# FPGA_POWER.net
KiCad netlist of a schematic drawn in Altium Designer
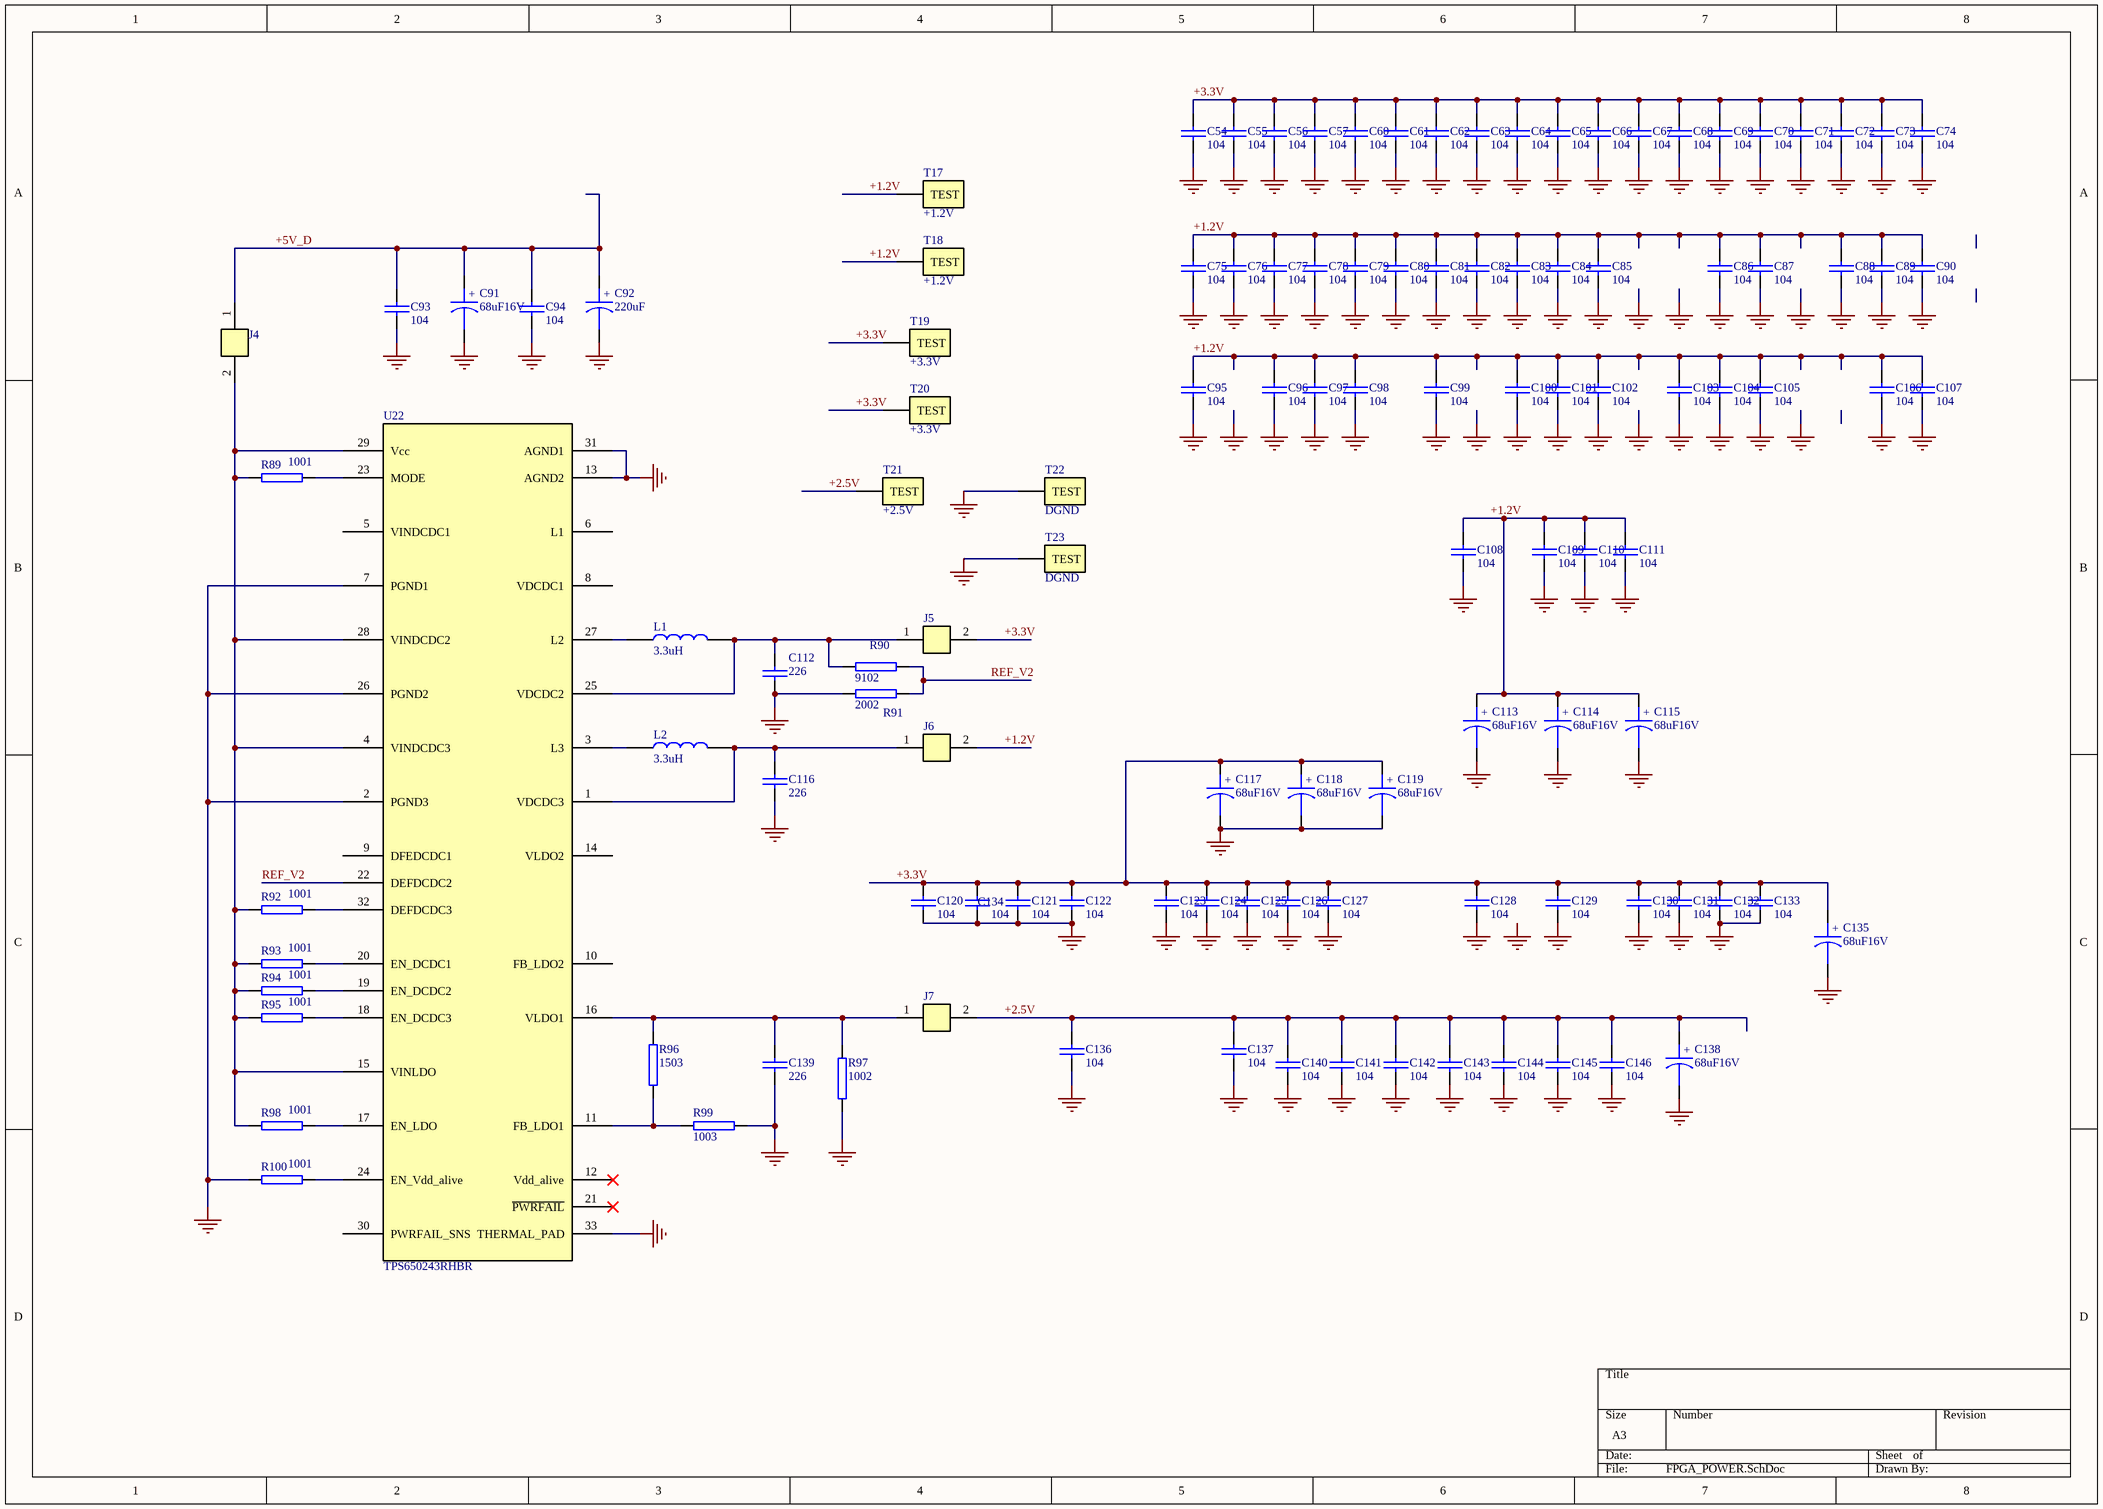
[diagram p0: FPGA_POWER.SchDoc]

(export (version "E")
  (design (tool "Eeschema 10.0.6"))
  (components
    (comp (ref "C54")
      (value "104")
      (footprint "0805C")
      (description "Capacitor")
      (libsource (lib "*") (part "CAP"))
    )
    (comp (ref "C55")
      (value "104")
      (footprint "0402C")
      (description "Capacitor")
      (libsource (lib "*") (part "CAP"))
    )
    (comp (ref "C56")
      (value "104")
      (footprint "0402C")
      (description "Capacitor")
      (libsource (lib "*") (part "CAP"))
    )
    (comp (ref "C57")
      (value "104")
      (footprint "0402C")
      (description "Capacitor")
      (libsource (lib "*") (part "CAP"))
    )
    (comp (ref "C60")
      (value "104")
      (footprint "0402C")
      (description "Capacitor")
      (libsource (lib "*") (part "CAP"))
    )
    (comp (ref "C61")
      (value "104")
      (footprint "0402C")
      (description "Capacitor")
      (libsource (lib "*") (part "CAP"))
    )
    (comp (ref "C62")
      (value "104")
      (footprint "0402C")
      (description "Capacitor")
      (libsource (lib "*") (part "CAP"))
    )
    (comp (ref "C63")
      (value "104")
      (footprint "0402C")
      (description "Capacitor")
      (libsource (lib "*") (part "CAP"))
    )
    (comp (ref "C64")
      (value "104")
      (footprint "0402C")
      (description "Capacitor")
      (libsource (lib "*") (part "CAP"))
    )
    (comp (ref "C65")
      (value "104")
      (footprint "0402C")
      (description "Capacitor")
      (libsource (lib "*") (part "CAP"))
    )
    (comp (ref "C66")
      (value "104")
      (footprint "0402C")
      (description "Capacitor")
      (libsource (lib "*") (part "CAP"))
    )
    (comp (ref "C67")
      (value "104")
      (footprint "0402C")
      (description "Capacitor")
      (libsource (lib "*") (part "CAP"))
    )
    (comp (ref "C68")
      (value "104")
      (footprint "0402C")
      (description "Capacitor")
      (libsource (lib "*") (part "CAP"))
    )
    (comp (ref "C69")
      (value "104")
      (footprint "0402C")
      (description "Capacitor")
      (libsource (lib "*") (part "CAP"))
    )
    (comp (ref "C70")
      (value "104")
      (footprint "0402C")
      (description "Capacitor")
      (libsource (lib "*") (part "CAP"))
    )
    (comp (ref "C71")
      (value "104")
      (footprint "0402C")
      (description "Capacitor")
      (libsource (lib "*") (part "CAP"))
    )
    (comp (ref "C72")
      (value "104")
      (footprint "0402C")
      (description "Capacitor")
      (libsource (lib "*") (part "CAP"))
    )
    (comp (ref "C73")
      (value "104")
      (footprint "0402C")
      (description "Capacitor")
      (libsource (lib "*") (part "CAP"))
    )
    (comp (ref "C74")
      (value "104")
      (footprint "0402C")
      (description "Capacitor")
      (libsource (lib "*") (part "CAP"))
    )
    (comp (ref "C75")
      (value "104")
      (footprint "0805C")
      (description "Capacitor")
      (libsource (lib "*") (part "CAP"))
    )
    (comp (ref "C76")
      (value "104")
      (footprint "0402C")
      (description "Capacitor")
      (libsource (lib "*") (part "CAP"))
    )
    (comp (ref "C77")
      (value "104")
      (footprint "0402C")
      (description "Capacitor")
      (libsource (lib "*") (part "CAP"))
    )
    (comp (ref "C78")
      (value "104")
      (footprint "0805C")
      (description "Capacitor")
      (libsource (lib "*") (part "CAP"))
    )
    (comp (ref "C79")
      (value "104")
      (footprint "0402C")
      (description "Capacitor")
      (libsource (lib "*") (part "CAP"))
    )
    (comp (ref "C80")
      (value "104")
      (footprint "0402C")
      (description "Capacitor")
      (libsource (lib "*") (part "CAP"))
    )
    (comp (ref "C81")
      (value "104")
      (footprint "0402C")
      (description "Capacitor")
      (libsource (lib "*") (part "CAP"))
    )
    (comp (ref "C82")
      (value "104")
      (footprint "0402C")
      (description "Capacitor")
      (libsource (lib "*") (part "CAP"))
    )
    (comp (ref "C83")
      (value "104")
      (footprint "0402C")
      (description "Capacitor")
      (libsource (lib "*") (part "CAP"))
    )
    (comp (ref "C84")
      (value "104")
      (footprint "0402C")
      (description "Capacitor")
      (libsource (lib "*") (part "CAP"))
    )
    (comp (ref "C85")
      (value "104")
      (footprint "0402C")
      (description "Capacitor")
      (libsource (lib "*") (part "CAP"))
    )
    (comp (ref "C86")
      (value "104")
      (footprint "0402C")
      (description "Capacitor")
      (libsource (lib "*") (part "CAP"))
    )
    (comp (ref "C87")
      (value "104")
      (footprint "0805C")
      (description "Capacitor")
      (libsource (lib "*") (part "CAP"))
    )
    (comp (ref "C88")
      (value "104")
      (footprint "0402C")
      (description "Capacitor")
      (libsource (lib "*") (part "CAP"))
    )
    (comp (ref "C89")
      (value "104")
      (footprint "0402C")
      (description "Capacitor")
      (libsource (lib "*") (part "CAP"))
    )
    (comp (ref "C90")
      (value "104")
      (footprint "0402C")
      (description "Capacitor")
      (libsource (lib "*") (part "CAP"))
    )
    (comp (ref "C91")
      (value "68uF16V")
      (footprint "6032")
      (description "Capacitor")
      (libsource (lib "*") (part "CAPACITOR POL"))
    )
    (comp (ref "C92")
      (value "220uF")
      (footprint "c200")
      (description "Capacitor")
      (libsource (lib "") (part "CAPACITOR POL_1"))
    )
    (comp (ref "C93")
      (value "104")
      (footprint "0805C")
      (description "Capacitor")
      (libsource (lib "*") (part "CAP"))
    )
    (comp (ref "C94")
      (value "104")
      (footprint "0805C")
      (description "Capacitor")
      (libsource (lib "*") (part "CAP"))
    )
    (comp (ref "C95")
      (value "104")
      (footprint "0402C")
      (description "Capacitor")
      (libsource (lib "*") (part "CAP"))
    )
    (comp (ref "C96")
      (value "104")
      (footprint "0402C")
      (description "Capacitor")
      (libsource (lib "*") (part "CAP"))
    )
    (comp (ref "C97")
      (value "104")
      (footprint "0402C")
      (description "Capacitor")
      (libsource (lib "*") (part "CAP"))
    )
    (comp (ref "C98")
      (value "104")
      (footprint "0402C")
      (description "Capacitor")
      (libsource (lib "*") (part "CAP"))
    )
    (comp (ref "C99")
      (value "104")
      (footprint "0402C")
      (description "Capacitor")
      (libsource (lib "*") (part "CAP"))
    )
    (comp (ref "C100")
      (value "104")
      (footprint "0402C")
      (description "Capacitor")
      (libsource (lib "*") (part "CAP"))
    )
    (comp (ref "C101")
      (value "104")
      (footprint "0402C")
      (description "Capacitor")
      (libsource (lib "*") (part "CAP"))
    )
    (comp (ref "C102")
      (value "104")
      (footprint "0402C")
      (description "Capacitor")
      (libsource (lib "*") (part "CAP"))
    )
    (comp (ref "C103")
      (value "104")
      (footprint "0402C")
      (description "Capacitor")
      (libsource (lib "*") (part "CAP"))
    )
    (comp (ref "C104")
      (value "104")
      (footprint "0402C")
      (description "Capacitor")
      (libsource (lib "*") (part "CAP"))
    )
    (comp (ref "C105")
      (value "104")
      (footprint "0805C")
      (description "Capacitor")
      (libsource (lib "*") (part "CAP"))
    )
    (comp (ref "C106")
      (value "104")
      (footprint "0402C")
      (description "Capacitor")
      (libsource (lib "*") (part "CAP"))
    )
    (comp (ref "C107")
      (value "104")
      (footprint "0402C")
      (description "Capacitor")
      (libsource (lib "*") (part "CAP"))
    )
    (comp (ref "C108")
      (value "104")
      (footprint "0402C")
      (description "Capacitor")
      (libsource (lib "*") (part "CAP"))
    )
    (comp (ref "C109")
      (value "104")
      (footprint "0402C")
      (description "Capacitor")
      (libsource (lib "*") (part "CAP"))
    )
    (comp (ref "C110")
      (value "104")
      (footprint "0402C")
      (description "Capacitor")
      (libsource (lib "*") (part "CAP"))
    )
    (comp (ref "C111")
      (value "104")
      (footprint "0402C")
      (description "Capacitor")
      (libsource (lib "*") (part "CAP"))
    )
    (comp (ref "C112")
      (value "226")
      (footprint "C226")
      (description "Capacitor")
      (libsource (lib "*") (part "CAP"))
    )
    (comp (ref "C113")
      (value "68uF16V")
      (footprint "6032")
      (description "Capacitor")
      (libsource (lib "*") (part "CAPACITOR POL"))
    )
    (comp (ref "C114")
      (value "68uF16V")
      (footprint "6032")
      (description "Capacitor")
      (libsource (lib "*") (part "CAPACITOR POL"))
    )
    (comp (ref "C115")
      (value "68uF16V")
      (footprint "6032")
      (description "Capacitor")
      (libsource (lib "*") (part "CAPACITOR POL"))
    )
    (comp (ref "C116")
      (value "226")
      (footprint "C226")
      (description "Capacitor")
      (libsource (lib "*") (part "CAP"))
    )
    (comp (ref "C117")
      (value "68uF16V")
      (footprint "6032")
      (description "Capacitor")
      (libsource (lib "*") (part "CAPACITOR POL"))
    )
    (comp (ref "C118")
      (value "68uF16V")
      (footprint "6032")
      (description "Capacitor")
      (libsource (lib "*") (part "CAPACITOR POL"))
    )
    (comp (ref "C119")
      (value "68uF16V")
      (footprint "6032")
      (description "Capacitor")
      (libsource (lib "*") (part "CAPACITOR POL"))
    )
    (comp (ref "C120")
      (value "104")
      (footprint "0402C")
      (description "Capacitor")
      (libsource (lib "*") (part "CAP"))
    )
    (comp (ref "C121")
      (value "104")
      (footprint "0402C")
      (description "Capacitor")
      (libsource (lib "*") (part "CAP"))
    )
    (comp (ref "C122")
      (value "104")
      (footprint "0805C")
      (description "Capacitor")
      (libsource (lib "*") (part "CAP"))
    )
    (comp (ref "C123")
      (value "104")
      (footprint "0805C")
      (description "Capacitor")
      (libsource (lib "*") (part "CAP"))
    )
    (comp (ref "C124")
      (value "104")
      (footprint "0805C")
      (description "Capacitor")
      (libsource (lib "*") (part "CAP"))
    )
    (comp (ref "C125")
      (value "104")
      (footprint "0805C")
      (description "Capacitor")
      (libsource (lib "*") (part "CAP"))
    )
    (comp (ref "C126")
      (value "104")
      (footprint "0805C")
      (description "Capacitor")
      (libsource (lib "*") (part "CAP"))
    )
    (comp (ref "C127")
      (value "104")
      (footprint "0402C")
      (description "Capacitor")
      (libsource (lib "*") (part "CAP"))
    )
    (comp (ref "C128")
      (value "104")
      (footprint "0805C")
      (description "Capacitor")
      (libsource (lib "*") (part "CAP"))
    )
    (comp (ref "C129")
      (value "104")
      (footprint "0402C")
      (description "Capacitor")
      (libsource (lib "*") (part "CAP"))
    )
    (comp (ref "C130")
      (value "104")
      (footprint "0402C")
      (description "Capacitor")
      (libsource (lib "*") (part "CAP"))
    )
    (comp (ref "C131")
      (value "104")
      (footprint "0402C")
      (description "Capacitor")
      (libsource (lib "*") (part "CAP"))
    )
    (comp (ref "C132")
      (value "104")
      (footprint "0402C")
      (description "Capacitor")
      (libsource (lib "*") (part "CAP"))
    )
    (comp (ref "C133")
      (value "104")
      (footprint "0402C")
      (description "Capacitor")
      (libsource (lib "*") (part "CAP"))
    )
    (comp (ref "C134")
      (value "104")
      (footprint "0402C")
      (description "Capacitor")
      (libsource (lib "*") (part "CAP"))
    )
    (comp (ref "C135")
      (value "68uF16V")
      (footprint "6032")
      (description "Capacitor")
      (libsource (lib "*") (part "CAPACITOR POL"))
    )
    (comp (ref "C136")
      (value "104")
      (footprint "0805C")
      (description "Capacitor")
      (libsource (lib "*") (part "CAP"))
    )
    (comp (ref "C137")
      (value "104")
      (footprint "0805C")
      (description "Capacitor")
      (libsource (lib "*") (part "CAP"))
    )
    (comp (ref "C138")
      (value "68uF16V")
      (footprint "6032")
      (description "Capacitor")
      (libsource (lib "*") (part "CAPACITOR POL"))
    )
    (comp (ref "C139")
      (value "226")
      (footprint "C226")
      (description "Capacitor")
      (libsource (lib "*") (part "CAP"))
    )
    (comp (ref "C140")
      (value "104")
      (footprint "0402C")
      (description "Capacitor")
      (libsource (lib "*") (part "CAP"))
    )
    (comp (ref "C141")
      (value "104")
      (footprint "0402C")
      (description "Capacitor")
      (libsource (lib "*") (part "CAP"))
    )
    (comp (ref "C142")
      (value "104")
      (footprint "0402C")
      (description "Capacitor")
      (libsource (lib "*") (part "CAP"))
    )
    (comp (ref "C143")
      (value "104")
      (footprint "0402C")
      (description "Capacitor")
      (libsource (lib "*") (part "CAP"))
    )
    (comp (ref "C144")
      (value "104")
      (footprint "0805C")
      (description "Capacitor")
      (libsource (lib "*") (part "CAP"))
    )
    (comp (ref "C145")
      (value "104")
      (footprint "0402C")
      (description "Capacitor")
      (libsource (lib "*") (part "CAP"))
    )
    (comp (ref "C146")
      (value "104")
      (footprint "0402C")
      (description "Capacitor")
      (libsource (lib "*") (part "CAP"))
    )
    (comp (ref "J4") (value "~") (footprint "I_ON1") (libsource (lib "*") (part "I_ON")))
    (comp (ref "J5") (value "~") (footprint "I_ON1") (libsource (lib "") (part "I_ON_1")))
    (comp (ref "J6") (value "~") (footprint "I_ON1") (libsource (lib "") (part "I_ON_1")))
    (comp (ref "J7") (value "~") (footprint "I_ON1") (libsource (lib "") (part "I_ON_1")))
    (comp (ref "L1") (value "3.3uH") (footprint "L3R3") (libsource (lib "*") (part "L")))
    (comp (ref "L2") (value "3.3uH") (footprint "L3R3") (libsource (lib "*") (part "L")))
    (comp (ref "R89") (value "1001") (footprint "0603") (libsource (lib "*") (part "RES2")))
    (comp (ref "R90") (value "9102") (footprint "0603") (libsource (lib "*") (part "RES2")))
    (comp (ref "R91") (value "2002") (footprint "0603") (libsource (lib "*") (part "RES2")))
    (comp (ref "R92") (value "1001") (footprint "0603") (libsource (lib "*") (part "RES2")))
    (comp (ref "R93") (value "1001") (footprint "0603") (libsource (lib "*") (part "RES2")))
    (comp (ref "R94") (value "1001") (footprint "0603") (libsource (lib "*") (part "RES2")))
    (comp (ref "R95") (value "1001") (footprint "0603") (libsource (lib "*") (part "RES2")))
    (comp (ref "R96") (value "1503") (footprint "0603") (libsource (lib "*") (part "RES2")))
    (comp (ref "R97") (value "1002") (footprint "0603") (libsource (lib "") (part "RES2_1")))
    (comp (ref "R98") (value "1001") (footprint "0603") (libsource (lib "*") (part "RES2")))
    (comp (ref "R99") (value "1003") (footprint "0603") (libsource (lib "*") (part "RES2")))
    (comp (ref "R100") (value "1001") (footprint "0603") (libsource (lib "*") (part "RES2")))
    (comp (ref "T17") (value "+1.2V") (footprint "TEST") (libsource (lib "USB30_Project") (part "TEST")))
    (comp (ref "T18") (value "+1.2V") (footprint "TEST") (libsource (lib "USB30_Project") (part "TEST")))
    (comp (ref "T19") (value "+3.3V") (footprint "TEST") (libsource (lib "USB30_Project") (part "TEST")))
    (comp (ref "T20") (value "+3.3V") (footprint "TEST") (libsource (lib "USB30_Project") (part "TEST")))
    (comp (ref "T21") (value "+2.5V") (footprint "TEST") (libsource (lib "USB30_Project") (part "TEST")))
    (comp (ref "T22") (value "DGND") (footprint "TEST") (libsource (lib "USB30_Project") (part "TEST")))
    (comp (ref "T23") (value "DGND") (footprint "TEST") (libsource (lib "USB30_Project") (part "TEST")))
    (comp (ref "U22") (value "TPS650243RHBR") (footprint "VQFN32") (libsource (lib "*") (part "TPS650243")))
  )
  (nets
    (net (code "1") (name "/+1.2V") (class "Default")
      (node (ref "C100") (pin "2") (pinfunction "2_2") (pintype "passive"))
      (node (ref "C101") (pin "2") (pinfunction "2_2") (pintype "passive"))
      (node (ref "C102") (pin "2") (pinfunction "2_2") (pintype "passive"))
      (node (ref "C103") (pin "2") (pinfunction "2_2") (pintype "passive"))
      (node (ref "C104") (pin "2") (pinfunction "2_2") (pintype "passive"))
      (node (ref "C105") (pin "2") (pinfunction "2_2") (pintype "passive"))
      (node (ref "C106") (pin "2") (pinfunction "2_2") (pintype "passive"))
      (node (ref "C107") (pin "2") (pinfunction "2_2") (pintype "passive"))
      (node (ref "C108") (pin "2") (pinfunction "2_2") (pintype "passive"))
      (node (ref "C109") (pin "2") (pinfunction "2_2") (pintype "passive"))
      (node (ref "C110") (pin "2") (pinfunction "2_2") (pintype "passive"))
      (node (ref "C111") (pin "2") (pinfunction "2_2") (pintype "passive"))
      (node (ref "C113") (pin "1") (pinfunction "1_1") (pintype "passive"))
      (node (ref "C114") (pin "1") (pinfunction "1_1") (pintype "passive"))
      (node (ref "C115") (pin "1") (pinfunction "1_1") (pintype "passive"))
      (node (ref "C75") (pin "2") (pinfunction "2_2") (pintype "passive"))
      (node (ref "C76") (pin "2") (pinfunction "2_2") (pintype "passive"))
      (node (ref "C77") (pin "2") (pinfunction "2_2") (pintype "passive"))
      (node (ref "C78") (pin "2") (pinfunction "2_2") (pintype "passive"))
      (node (ref "C79") (pin "2") (pinfunction "2_2") (pintype "passive"))
      (node (ref "C80") (pin "2") (pinfunction "2_2") (pintype "passive"))
      (node (ref "C81") (pin "2") (pinfunction "2_2") (pintype "passive"))
      (node (ref "C82") (pin "2") (pinfunction "2_2") (pintype "passive"))
      (node (ref "C83") (pin "2") (pinfunction "2_2") (pintype "passive"))
      (node (ref "C84") (pin "2") (pinfunction "2_2") (pintype "passive"))
      (node (ref "C85") (pin "2") (pinfunction "2_2") (pintype "passive"))
      (node (ref "C86") (pin "2") (pinfunction "2_2") (pintype "passive"))
      (node (ref "C87") (pin "2") (pinfunction "2_2") (pintype "passive"))
      (node (ref "C88") (pin "2") (pinfunction "2_2") (pintype "passive"))
      (node (ref "C89") (pin "2") (pinfunction "2_2") (pintype "passive"))
      (node (ref "C90") (pin "2") (pinfunction "2_2") (pintype "passive"))
      (node (ref "C95") (pin "2") (pinfunction "2_2") (pintype "passive"))
      (node (ref "C96") (pin "2") (pinfunction "2_2") (pintype "passive"))
      (node (ref "C97") (pin "2") (pinfunction "2_2") (pintype "passive"))
      (node (ref "C98") (pin "2") (pinfunction "2_2") (pintype "passive"))
      (node (ref "C99") (pin "2") (pinfunction "2_2") (pintype "passive"))
      (node (ref "J6") (pin "2") (pintype "passive"))
      (node (ref "T17") (pin "1") (pinfunction "TEST_1") (pintype "passive"))
      (node (ref "T18") (pin "1") (pinfunction "TEST_1") (pintype "passive"))
    )
    (net (code "2") (name "/+2.5V") (class "Default")
      (node (ref "C136") (pin "2") (pinfunction "2_2") (pintype "passive"))
      (node (ref "C137") (pin "2") (pinfunction "2_2") (pintype "passive"))
      (node (ref "C138") (pin "1") (pinfunction "1_1") (pintype "passive"))
      (node (ref "C140") (pin "2") (pinfunction "2_2") (pintype "passive"))
      (node (ref "C141") (pin "2") (pinfunction "2_2") (pintype "passive"))
      (node (ref "C142") (pin "2") (pinfunction "2_2") (pintype "passive"))
      (node (ref "C143") (pin "2") (pinfunction "2_2") (pintype "passive"))
      (node (ref "C144") (pin "2") (pinfunction "2_2") (pintype "passive"))
      (node (ref "C145") (pin "2") (pinfunction "2_2") (pintype "passive"))
      (node (ref "C146") (pin "2") (pinfunction "2_2") (pintype "passive"))
      (node (ref "J7") (pin "2") (pintype "passive"))
      (node (ref "T21") (pin "1") (pinfunction "TEST_1") (pintype "passive"))
    )
    (net (code "3") (name "/+3.3V") (class "Default")
      (node (ref "C117") (pin "1") (pinfunction "1_1") (pintype "passive"))
      (node (ref "C118") (pin "1") (pinfunction "1_1") (pintype "passive"))
      (node (ref "C119") (pin "1") (pinfunction "1_1") (pintype "passive"))
      (node (ref "C120") (pin "2") (pinfunction "2_2") (pintype "passive"))
      (node (ref "C121") (pin "2") (pinfunction "2_2") (pintype "passive"))
      (node (ref "C122") (pin "2") (pinfunction "2_2") (pintype "passive"))
      (node (ref "C123") (pin "2") (pinfunction "2_2") (pintype "passive"))
      (node (ref "C124") (pin "2") (pinfunction "2_2") (pintype "passive"))
      (node (ref "C125") (pin "2") (pinfunction "2_2") (pintype "passive"))
      (node (ref "C126") (pin "2") (pinfunction "2_2") (pintype "passive"))
      (node (ref "C127") (pin "2") (pinfunction "2_2") (pintype "passive"))
      (node (ref "C128") (pin "2") (pinfunction "2_2") (pintype "passive"))
      (node (ref "C129") (pin "2") (pinfunction "2_2") (pintype "passive"))
      (node (ref "C130") (pin "2") (pinfunction "2_2") (pintype "passive"))
      (node (ref "C131") (pin "2") (pinfunction "2_2") (pintype "passive"))
      (node (ref "C132") (pin "2") (pinfunction "2_2") (pintype "passive"))
      (node (ref "C133") (pin "2") (pinfunction "2_2") (pintype "passive"))
      (node (ref "C134") (pin "2") (pinfunction "2_2") (pintype "passive"))
      (node (ref "C135") (pin "1") (pinfunction "1_1") (pintype "passive"))
      (node (ref "C54") (pin "2") (pinfunction "2_2") (pintype "passive"))
      (node (ref "C55") (pin "2") (pinfunction "2_2") (pintype "passive"))
      (node (ref "C56") (pin "2") (pinfunction "2_2") (pintype "passive"))
      (node (ref "C57") (pin "2") (pinfunction "2_2") (pintype "passive"))
      (node (ref "C60") (pin "2") (pinfunction "2_2") (pintype "passive"))
      (node (ref "C61") (pin "2") (pinfunction "2_2") (pintype "passive"))
      (node (ref "C62") (pin "2") (pinfunction "2_2") (pintype "passive"))
      (node (ref "C63") (pin "2") (pinfunction "2_2") (pintype "passive"))
      (node (ref "C64") (pin "2") (pinfunction "2_2") (pintype "passive"))
      (node (ref "C65") (pin "2") (pinfunction "2_2") (pintype "passive"))
      (node (ref "C66") (pin "2") (pinfunction "2_2") (pintype "passive"))
      (node (ref "C67") (pin "2") (pinfunction "2_2") (pintype "passive"))
      (node (ref "C68") (pin "2") (pinfunction "2_2") (pintype "passive"))
      (node (ref "C69") (pin "2") (pinfunction "2_2") (pintype "passive"))
      (node (ref "C70") (pin "2") (pinfunction "2_2") (pintype "passive"))
      (node (ref "C71") (pin "2") (pinfunction "2_2") (pintype "passive"))
      (node (ref "C72") (pin "2") (pinfunction "2_2") (pintype "passive"))
      (node (ref "C73") (pin "2") (pinfunction "2_2") (pintype "passive"))
      (node (ref "C74") (pin "2") (pinfunction "2_2") (pintype "passive"))
      (node (ref "J5") (pin "2") (pintype "passive"))
      (node (ref "T19") (pin "1") (pinfunction "TEST_1") (pintype "passive"))
      (node (ref "T20") (pin "1") (pinfunction "TEST_1") (pintype "passive"))
    )
    (net (code "4") (name "/+5V_D") (class "Default")
      (node (ref "C91") (pin "1") (pinfunction "1_1") (pintype "passive"))
      (node (ref "C92") (pin "1") (pinfunction "1_1") (pintype "passive"))
      (node (ref "C93") (pin "2") (pinfunction "2_2") (pintype "passive"))
      (node (ref "C94") (pin "2") (pinfunction "2_2") (pintype "passive"))
      (node (ref "J4") (pin "1") (pintype "passive"))
    )
    (net (code "5") (name "/REF_V2") (class "Default")
      (node (ref "R90") (pin "2") (pinfunction "2_2") (pintype "passive"))
      (node (ref "R91") (pin "1") (pinfunction "1_1") (pintype "passive"))
      (node (ref "U22") (pin "22") (pinfunction "DEFDCDC2_22") (pintype "passive"))
    )
    (net (code "6") (name "DGND") (class "Default")
      (node (ref "C100") (pin "1") (pinfunction "1_1") (pintype "passive"))
      (node (ref "C101") (pin "1") (pinfunction "1_1") (pintype "passive"))
      (node (ref "C102") (pin "1") (pinfunction "1_1") (pintype "passive"))
      (node (ref "C103") (pin "1") (pinfunction "1_1") (pintype "passive"))
      (node (ref "C104") (pin "1") (pinfunction "1_1") (pintype "passive"))
      (node (ref "C105") (pin "1") (pinfunction "1_1") (pintype "passive"))
      (node (ref "C106") (pin "1") (pinfunction "1_1") (pintype "passive"))
      (node (ref "C107") (pin "1") (pinfunction "1_1") (pintype "passive"))
      (node (ref "C108") (pin "1") (pinfunction "1_1") (pintype "passive"))
      (node (ref "C109") (pin "1") (pinfunction "1_1") (pintype "passive"))
      (node (ref "C110") (pin "1") (pinfunction "1_1") (pintype "passive"))
      (node (ref "C111") (pin "1") (pinfunction "1_1") (pintype "passive"))
      (node (ref "C112") (pin "2") (pinfunction "2_2") (pintype "passive"))
      (node (ref "C113") (pin "2") (pinfunction "2_2") (pintype "passive"))
      (node (ref "C114") (pin "2") (pinfunction "2_2") (pintype "passive"))
      (node (ref "C115") (pin "2") (pinfunction "2_2") (pintype "passive"))
      (node (ref "C116") (pin "2") (pinfunction "2_2") (pintype "passive"))
      (node (ref "C117") (pin "2") (pinfunction "2_2") (pintype "passive"))
      (node (ref "C118") (pin "2") (pinfunction "2_2") (pintype "passive"))
      (node (ref "C119") (pin "2") (pinfunction "2_2") (pintype "passive"))
      (node (ref "C120") (pin "1") (pinfunction "1_1") (pintype "passive"))
      (node (ref "C121") (pin "1") (pinfunction "1_1") (pintype "passive"))
      (node (ref "C122") (pin "1") (pinfunction "1_1") (pintype "passive"))
      (node (ref "C123") (pin "1") (pinfunction "1_1") (pintype "passive"))
      (node (ref "C124") (pin "1") (pinfunction "1_1") (pintype "passive"))
      (node (ref "C125") (pin "1") (pinfunction "1_1") (pintype "passive"))
      (node (ref "C126") (pin "1") (pinfunction "1_1") (pintype "passive"))
      (node (ref "C127") (pin "1") (pinfunction "1_1") (pintype "passive"))
      (node (ref "C128") (pin "1") (pinfunction "1_1") (pintype "passive"))
      (node (ref "C129") (pin "1") (pinfunction "1_1") (pintype "passive"))
      (node (ref "C130") (pin "1") (pinfunction "1_1") (pintype "passive"))
      (node (ref "C131") (pin "1") (pinfunction "1_1") (pintype "passive"))
      (node (ref "C132") (pin "1") (pinfunction "1_1") (pintype "passive"))
      (node (ref "C133") (pin "1") (pinfunction "1_1") (pintype "passive"))
      (node (ref "C134") (pin "1") (pinfunction "1_1") (pintype "passive"))
      (node (ref "C135") (pin "2") (pinfunction "2_2") (pintype "passive"))
      (node (ref "C136") (pin "1") (pinfunction "1_1") (pintype "passive"))
      (node (ref "C137") (pin "1") (pinfunction "1_1") (pintype "passive"))
      (node (ref "C138") (pin "2") (pinfunction "2_2") (pintype "passive"))
      (node (ref "C139") (pin "2") (pinfunction "2_2") (pintype "passive"))
      (node (ref "C140") (pin "1") (pinfunction "1_1") (pintype "passive"))
      (node (ref "C141") (pin "1") (pinfunction "1_1") (pintype "passive"))
      (node (ref "C142") (pin "1") (pinfunction "1_1") (pintype "passive"))
      (node (ref "C143") (pin "1") (pinfunction "1_1") (pintype "passive"))
      (node (ref "C144") (pin "1") (pinfunction "1_1") (pintype "passive"))
      (node (ref "C145") (pin "1") (pinfunction "1_1") (pintype "passive"))
      (node (ref "C146") (pin "1") (pinfunction "1_1") (pintype "passive"))
      (node (ref "C54") (pin "1") (pinfunction "1_1") (pintype "passive"))
      (node (ref "C55") (pin "1") (pinfunction "1_1") (pintype "passive"))
      (node (ref "C56") (pin "1") (pinfunction "1_1") (pintype "passive"))
      (node (ref "C57") (pin "1") (pinfunction "1_1") (pintype "passive"))
      (node (ref "C60") (pin "1") (pinfunction "1_1") (pintype "passive"))
      (node (ref "C61") (pin "1") (pinfunction "1_1") (pintype "passive"))
      (node (ref "C62") (pin "1") (pinfunction "1_1") (pintype "passive"))
      (node (ref "C63") (pin "1") (pinfunction "1_1") (pintype "passive"))
      (node (ref "C64") (pin "1") (pinfunction "1_1") (pintype "passive"))
      (node (ref "C65") (pin "1") (pinfunction "1_1") (pintype "passive"))
      (node (ref "C66") (pin "1") (pinfunction "1_1") (pintype "passive"))
      (node (ref "C67") (pin "1") (pinfunction "1_1") (pintype "passive"))
      (node (ref "C68") (pin "1") (pinfunction "1_1") (pintype "passive"))
      (node (ref "C69") (pin "1") (pinfunction "1_1") (pintype "passive"))
      (node (ref "C70") (pin "1") (pinfunction "1_1") (pintype "passive"))
      (node (ref "C71") (pin "1") (pinfunction "1_1") (pintype "passive"))
      (node (ref "C72") (pin "1") (pinfunction "1_1") (pintype "passive"))
      (node (ref "C73") (pin "1") (pinfunction "1_1") (pintype "passive"))
      (node (ref "C74") (pin "1") (pinfunction "1_1") (pintype "passive"))
      (node (ref "C75") (pin "1") (pinfunction "1_1") (pintype "passive"))
      (node (ref "C76") (pin "1") (pinfunction "1_1") (pintype "passive"))
      (node (ref "C77") (pin "1") (pinfunction "1_1") (pintype "passive"))
      (node (ref "C78") (pin "1") (pinfunction "1_1") (pintype "passive"))
      (node (ref "C79") (pin "1") (pinfunction "1_1") (pintype "passive"))
      (node (ref "C80") (pin "1") (pinfunction "1_1") (pintype "passive"))
      (node (ref "C81") (pin "1") (pinfunction "1_1") (pintype "passive"))
      (node (ref "C82") (pin "1") (pinfunction "1_1") (pintype "passive"))
      (node (ref "C83") (pin "1") (pinfunction "1_1") (pintype "passive"))
      (node (ref "C84") (pin "1") (pinfunction "1_1") (pintype "passive"))
      (node (ref "C85") (pin "1") (pinfunction "1_1") (pintype "passive"))
      (node (ref "C86") (pin "1") (pinfunction "1_1") (pintype "passive"))
      (node (ref "C87") (pin "1") (pinfunction "1_1") (pintype "passive"))
      (node (ref "C88") (pin "1") (pinfunction "1_1") (pintype "passive"))
      (node (ref "C89") (pin "1") (pinfunction "1_1") (pintype "passive"))
      (node (ref "C90") (pin "1") (pinfunction "1_1") (pintype "passive"))
      (node (ref "C91") (pin "2") (pinfunction "2_2") (pintype "passive"))
      (node (ref "C92") (pin "2") (pinfunction "2_2") (pintype "passive"))
      (node (ref "C93") (pin "1") (pinfunction "1_1") (pintype "passive"))
      (node (ref "C94") (pin "1") (pinfunction "1_1") (pintype "passive"))
      (node (ref "C95") (pin "1") (pinfunction "1_1") (pintype "passive"))
      (node (ref "C96") (pin "1") (pinfunction "1_1") (pintype "passive"))
      (node (ref "C97") (pin "1") (pinfunction "1_1") (pintype "passive"))
      (node (ref "C98") (pin "1") (pinfunction "1_1") (pintype "passive"))
      (node (ref "C99") (pin "1") (pinfunction "1_1") (pintype "passive"))
      (node (ref "R100") (pin "1") (pinfunction "1_1") (pintype "passive"))
      (node (ref "R91") (pin "2") (pinfunction "2_2") (pintype "passive"))
      (node (ref "R97") (pin "2") (pinfunction "2_2") (pintype "passive"))
      (node (ref "R99") (pin "2") (pinfunction "2_2") (pintype "passive"))
      (node (ref "T22") (pin "1") (pinfunction "TEST_1") (pintype "passive"))
      (node (ref "T23") (pin "1") (pinfunction "TEST_1") (pintype "passive"))
      (node (ref "U22") (pin "13") (pinfunction "AGND2_13") (pintype "passive"))
      (node (ref "U22") (pin "2") (pinfunction "PGND3_2") (pintype "passive"))
      (node (ref "U22") (pin "26") (pinfunction "PGND2_26") (pintype "passive"))
      (node (ref "U22") (pin "31") (pinfunction "AGND1_31") (pintype "passive"))
      (node (ref "U22") (pin "33") (pinfunction "THERMAL_PAD_33") (pintype "passive"))
      (node (ref "U22") (pin "7") (pinfunction "PGND1_7") (pintype "passive"))
    )
    (net (code "7") (name "Net-(U22-DEFDCDC3)") (class "Default")
      (node (ref "R92") (pin "2") (pinfunction "2_2") (pintype "passive"))
      (node (ref "U22") (pin "32") (pinfunction "DEFDCDC3_32") (pintype "passive"))
    )
    (net (code "8") (name "Net-(U22-EN_DCDC1)") (class "Default")
      (node (ref "R93") (pin "2") (pinfunction "2_2") (pintype "passive"))
      (node (ref "U22") (pin "20") (pinfunction "EN_DCDC1_20") (pintype "passive"))
    )
    (net (code "9") (name "Net-(U22-EN_DCDC2)") (class "Default")
      (node (ref "R94") (pin "2") (pinfunction "2_2") (pintype "passive"))
      (node (ref "U22") (pin "19") (pinfunction "EN_DCDC2_19") (pintype "passive"))
    )
    (net (code "10") (name "Net-(U22-EN_DCDC3)") (class "Default")
      (node (ref "R95") (pin "2") (pinfunction "2_2") (pintype "passive"))
      (node (ref "U22") (pin "18") (pinfunction "EN_DCDC3_18") (pintype "passive"))
    )
    (net (code "11") (name "Net-(U22-EN_LDO)") (class "Default")
      (node (ref "R98") (pin "2") (pinfunction "2_2") (pintype "passive"))
      (node (ref "U22") (pin "17") (pinfunction "EN_LDO_17") (pintype "passive"))
    )
    (net (code "12") (name "Net-(U22-EN_Vdd_alive)") (class "Default")
      (node (ref "R100") (pin "2") (pinfunction "2_2") (pintype "passive"))
      (node (ref "U22") (pin "24") (pinfunction "EN_Vdd_alive_24") (pintype "passive"))
    )
    (net (code "13") (name "Net-(U22-FB_LDO1)") (class "Default")
      (node (ref "R96") (pin "1") (pinfunction "1_1") (pintype "passive"))
      (node (ref "R99") (pin "1") (pinfunction "1_1") (pintype "passive"))
      (node (ref "U22") (pin "11") (pinfunction "FB_LDO1_11") (pintype "passive"))
    )
    (net (code "14") (name "Net-(U22-L2)") (class "Default")
      (node (ref "L1") (pin "1") (pinfunction "1_1") (pintype "passive"))
      (node (ref "U22") (pin "27") (pinfunction "L2_27") (pintype "passive"))
    )
    (net (code "15") (name "Net-(U22-L3)") (class "Default")
      (node (ref "L2") (pin "1") (pinfunction "1_1") (pintype "passive"))
      (node (ref "U22") (pin "3") (pinfunction "L3_3") (pintype "passive"))
    )
    (net (code "16") (name "Net-(U22-MODE)") (class "Default")
      (node (ref "R89") (pin "2") (pinfunction "2_2") (pintype "passive"))
      (node (ref "U22") (pin "23") (pinfunction "MODE_23") (pintype "passive"))
    )
    (net (code "17") (name "Net-(U22-VDCDC2)") (class "Default")
      (node (ref "C112") (pin "1") (pinfunction "1_1") (pintype "passive"))
      (node (ref "J5") (pin "1") (pintype "passive"))
      (node (ref "L1") (pin "2") (pinfunction "2_2") (pintype "passive"))
      (node (ref "R90") (pin "1") (pinfunction "1_1") (pintype "passive"))
      (node (ref "U22") (pin "25") (pinfunction "VDCDC2_25") (pintype "passive"))
    )
    (net (code "18") (name "Net-(U22-VDCDC3)") (class "Default")
      (node (ref "C116") (pin "1") (pinfunction "1_1") (pintype "passive"))
      (node (ref "J6") (pin "1") (pintype "passive"))
      (node (ref "L2") (pin "2") (pinfunction "2_2") (pintype "passive"))
      (node (ref "U22") (pin "1") (pinfunction "VDCDC3_1") (pintype "passive"))
    )
    (net (code "19") (name "Net-(U22-VINDCDC2)") (class "Default")
      (node (ref "J4") (pin "2") (pintype "passive"))
      (node (ref "R89") (pin "1") (pinfunction "1_1") (pintype "passive"))
      (node (ref "R92") (pin "1") (pinfunction "1_1") (pintype "passive"))
      (node (ref "R93") (pin "1") (pinfunction "1_1") (pintype "passive"))
      (node (ref "R94") (pin "1") (pinfunction "1_1") (pintype "passive"))
      (node (ref "R95") (pin "1") (pinfunction "1_1") (pintype "passive"))
      (node (ref "R98") (pin "1") (pinfunction "1_1") (pintype "passive"))
      (node (ref "U22") (pin "15") (pinfunction "VINLDO_15") (pintype "passive"))
      (node (ref "U22") (pin "28") (pinfunction "VINDCDC2_28") (pintype "passive"))
      (node (ref "U22") (pin "29") (pinfunction "Vcc_29") (pintype "passive"))
      (node (ref "U22") (pin "4") (pinfunction "VINDCDC3_4") (pintype "passive"))
    )
    (net (code "20") (name "Net-(U22-VLDO1)") (class "Default")
      (node (ref "C139") (pin "1") (pinfunction "1_1") (pintype "passive"))
      (node (ref "J7") (pin "1") (pintype "passive"))
      (node (ref "R96") (pin "2") (pinfunction "2_2") (pintype "passive"))
      (node (ref "R97") (pin "1") (pinfunction "1_1") (pintype "passive"))
      (node (ref "U22") (pin "16") (pinfunction "VLDO1_16") (pintype "passive"))
    )
    (net (code "21") (name "unconnected-(U22-DFEDCDC1-Pad9)") (class "Default")
      (node (ref "U22") (pin "9") (pinfunction "DFEDCDC1_9") (pintype "passive"))
    )
    (net (code "22") (name "unconnected-(U22-FB_LDO2-Pad10)") (class "Default")
      (node (ref "U22") (pin "10") (pinfunction "FB_LDO2_10") (pintype "passive"))
    )
    (net (code "23") (name "unconnected-(U22-L1-Pad6)") (class "Default")
      (node (ref "U22") (pin "6") (pinfunction "L1_6") (pintype "passive"))
    )
    (net (code "24") (name "unconnected-(U22-PWRFAIL_SNS-Pad30)") (class "Default")
      (node (ref "U22") (pin "30") (pinfunction "PWRFAIL_SNS_30") (pintype "passive"))
    )
    (net (code "25") (name "unconnected-(U22-VDCDC1-Pad8)") (class "Default")
      (node (ref "U22") (pin "8") (pinfunction "VDCDC1_8") (pintype "passive"))
    )
    (net (code "26") (name "unconnected-(U22-VINDCDC1-Pad5)") (class "Default")
      (node (ref "U22") (pin "5") (pinfunction "VINDCDC1_5") (pintype "passive"))
    )
    (net (code "27") (name "unconnected-(U22-VLDO2-Pad14)") (class "Default")
      (node (ref "U22") (pin "14") (pinfunction "VLDO2_14") (pintype "passive"))
    )
    (net (code "28") (name "unconnected-(U22-Vdd_alive-Pad12)") (class "Default")
      (node (ref "U22") (pin "12") (pinfunction "Vdd_alive_12") (pintype "passive+no_connect"))
    )
    (net (code "29") (name "unconnected-(U22-~{PWRFAIL}-Pad21)") (class "Default")
      (node (ref "U22") (pin "21") (pinfunction "~{PWRFAIL}_21") (pintype "passive+no_connect"))
    )
  )
)
